# SCH_Flight-Computer-V4_2024-07-19.net
KiCad netlist of a schematic drawn in EasyEDA
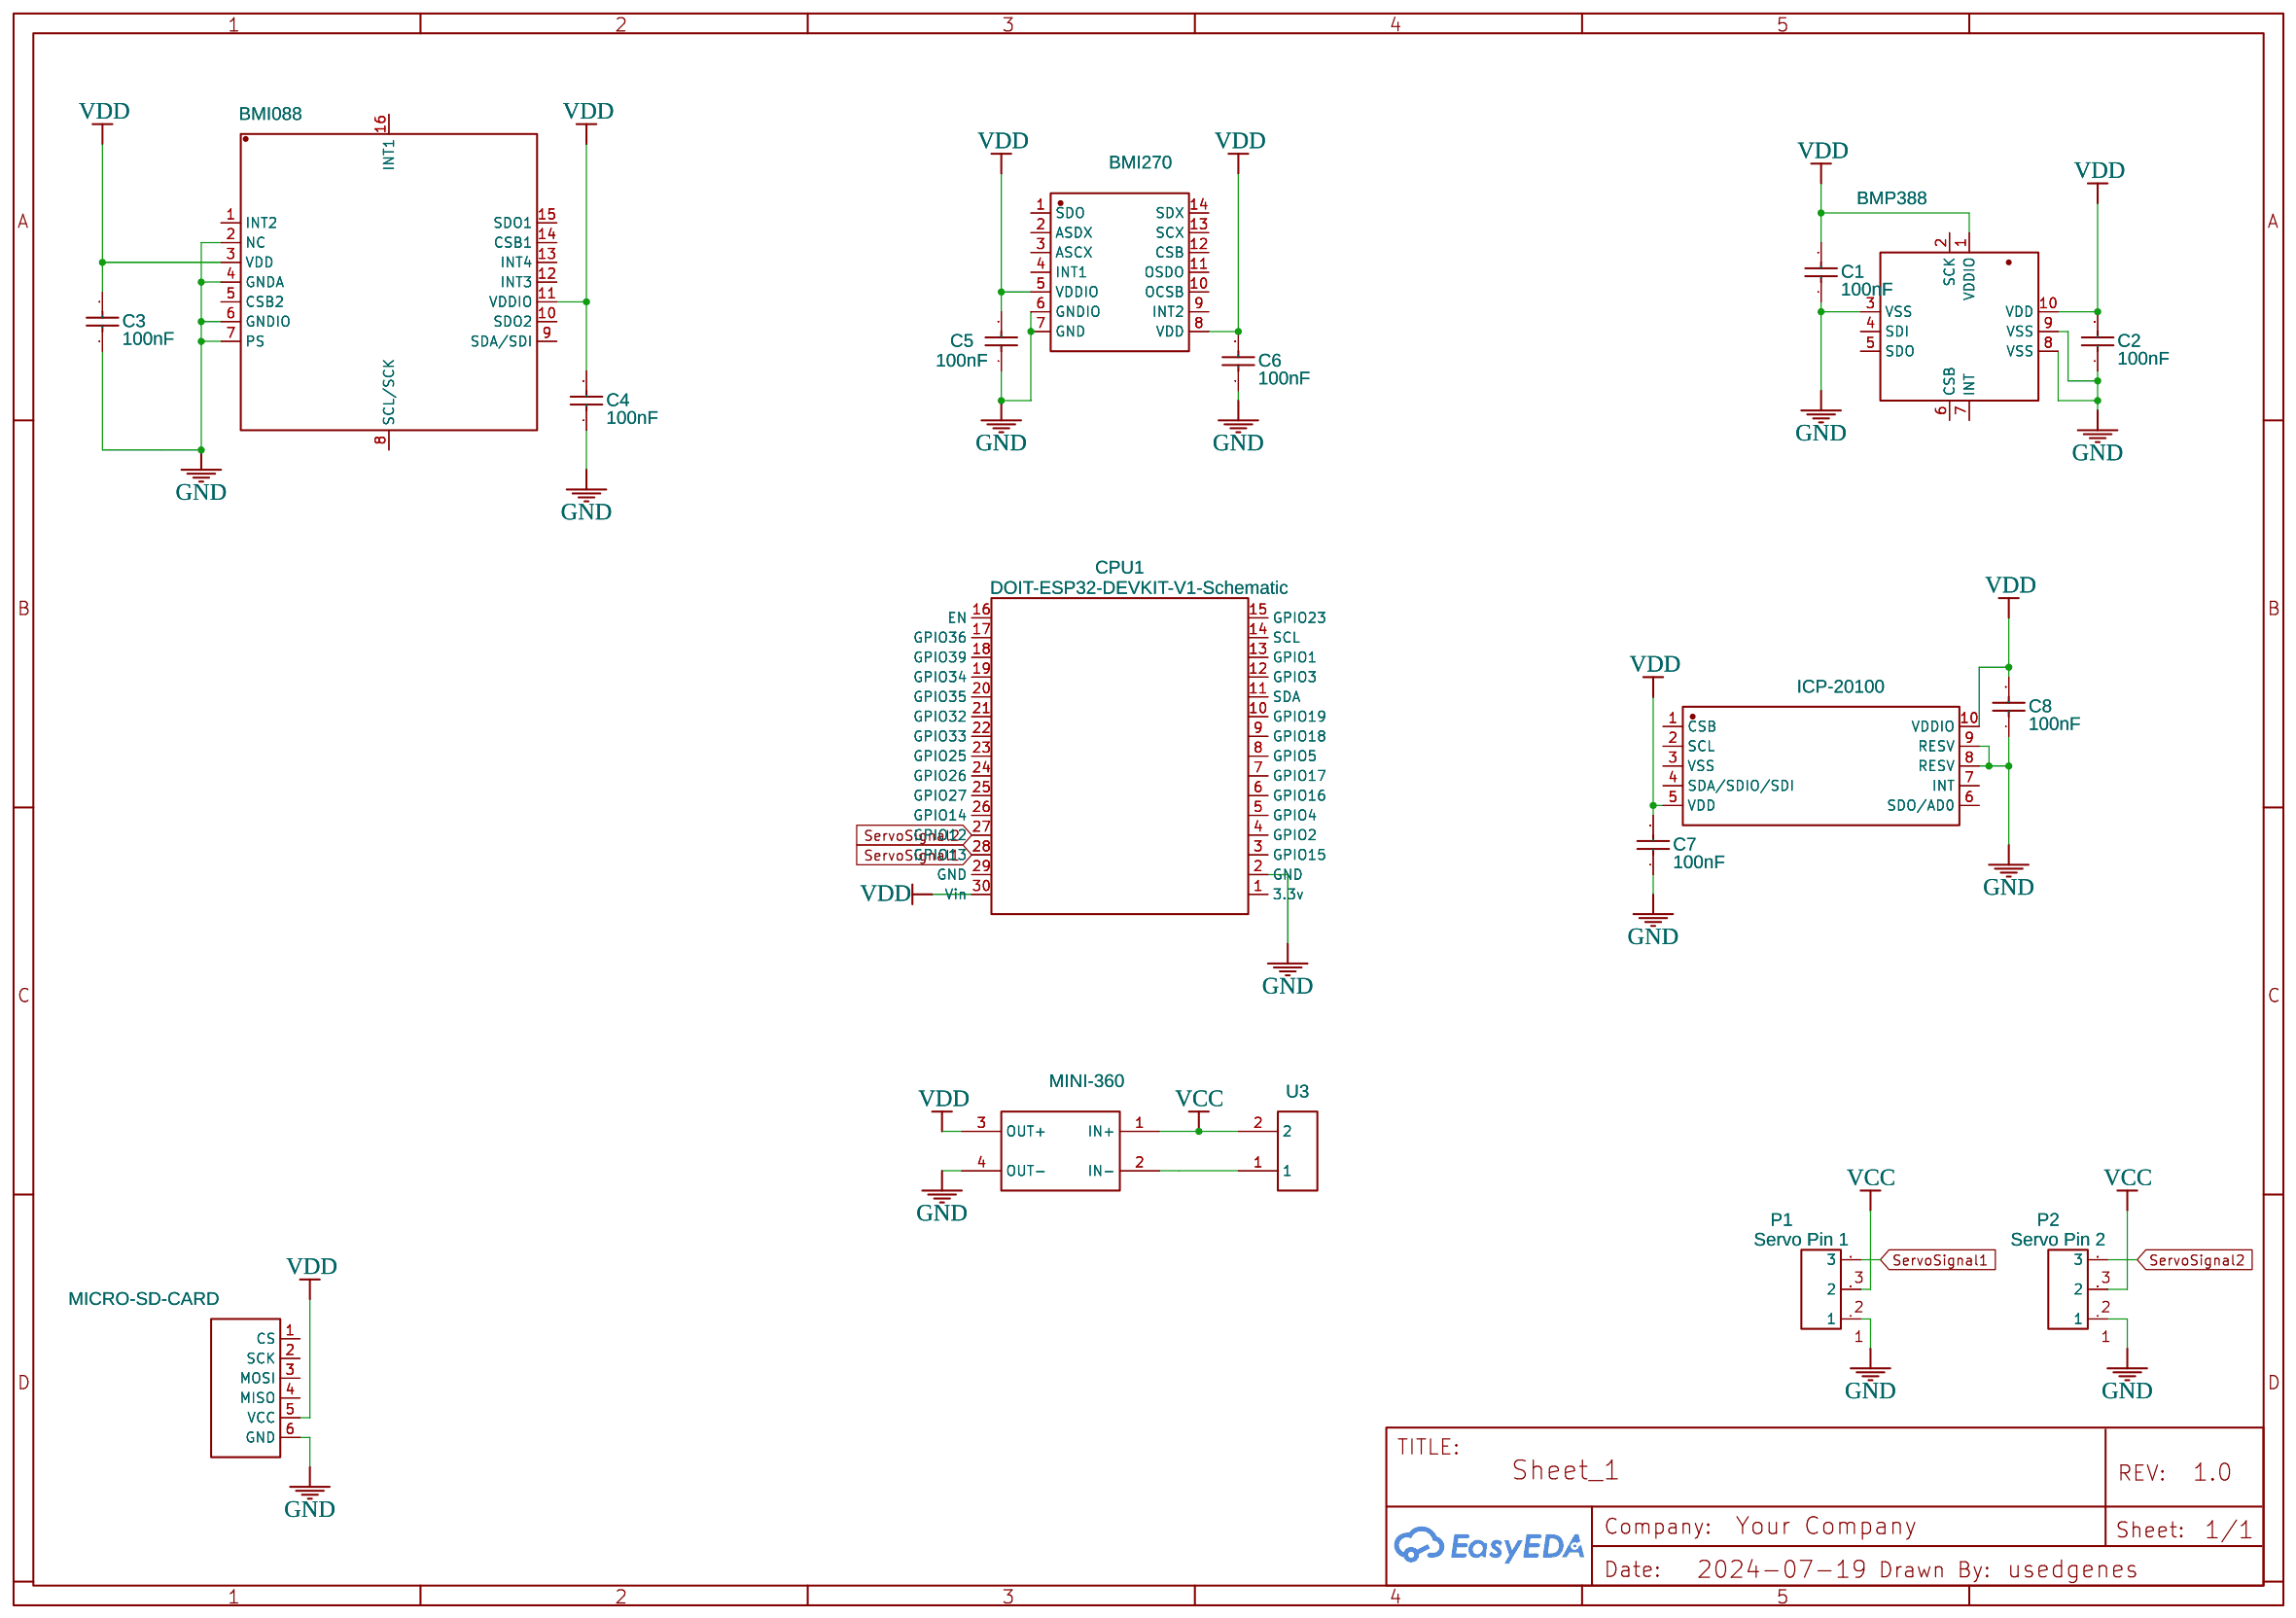
[diagram p0: schematic sheet]

(export (version "E")
  (design (tool "Eeschema 10.0.6"))
  (components
    (comp (ref "BMI088")
      (value "BMI088")
      (fields (field (name "Manufacturer") "Bosch(博世)"))
      (libsource (lib "") (part "BMI088"))
    )
    (comp (ref "BMI270")
      (value "BMI270")
      (fields (field (name "Manufacturer") "Bosch(博世)"))
      (libsource (lib "") (part "BMI270"))
    )
    (comp (ref "BMP388")
      (value "BMP388")
      (fields (field (name "Manufacturer") "Bosch(博世)"))
      (libsource (lib "") (part "BMP388"))
    )
    (comp (ref "C1")
      (value "100nF")
      (fields
        (field (name "Manufacturer Part") "CL05B104KO5NNNC")
        (field (name "Manufacturer") "SAMSUNG(三星)")
      )
      (libsource (lib "") (part "CL05B104KO5NNNC"))
    )
    (comp (ref "C2")
      (value "100nF")
      (fields
        (field (name "Manufacturer Part") "CL05B104KO5NNNC")
        (field (name "Manufacturer") "SAMSUNG(三星)")
      )
      (libsource (lib "") (part "CL05B104KO5NNNC"))
    )
    (comp (ref "C3")
      (value "100nF")
      (fields
        (field (name "Manufacturer Part") "CL05B104KO5NNNC")
        (field (name "Manufacturer") "SAMSUNG(三星)")
      )
      (libsource (lib "") (part "CL05B104KO5NNNC"))
    )
    (comp (ref "C4")
      (value "100nF")
      (fields
        (field (name "Manufacturer Part") "CL05B104KO5NNNC")
        (field (name "Manufacturer") "SAMSUNG(三星)")
      )
      (libsource (lib "") (part "CL05B104KO5NNNC"))
    )
    (comp (ref "C5")
      (value "100nF")
      (fields
        (field (name "Manufacturer Part") "CL05B104KO5NNNC")
        (field (name "Manufacturer") "SAMSUNG(三星)")
      )
      (libsource (lib "") (part "CL05B104KO5NNNC"))
    )
    (comp (ref "C6")
      (value "100nF")
      (fields
        (field (name "Manufacturer Part") "CL05B104KO5NNNC")
        (field (name "Manufacturer") "SAMSUNG(三星)")
      )
      (libsource (lib "") (part "CL05B104KO5NNNC"))
    )
    (comp (ref "C7")
      (value "100nF")
      (fields
        (field (name "Manufacturer Part") "CL05B104KO5NNNC")
        (field (name "Manufacturer") "SAMSUNG(三星)")
      )
      (libsource (lib "") (part "CL05B104KO5NNNC"))
    )
    (comp (ref "C8")
      (value "100nF")
      (fields
        (field (name "Manufacturer Part") "CL05B104KO5NNNC")
        (field (name "Manufacturer") "SAMSUNG(三星)")
      )
      (libsource (lib "") (part "CL05B104KO5NNNC"))
    )
    (comp (ref "CPU1")
      (value "DOIT-ESP32-DEVKIT-V1-Schematic")
      (fields (field (name "Manufacturer Part") "NONE"))
      (libsource (lib "") (part "DOIT-ESP32-DEVKIT-V1-Schematic"))
    )
    (comp (ref "ICP-20100")
      (value "ICP-20100")
      (fields (field (name "Manufacturer") "TDK"))
      (libsource (lib "") (part "ICP-20100"))
    )
    (comp (ref "MICRO-SD-CARD") (value "MicroSDCardAdapter") (libsource (lib "") (part "MicroSDCardAdapter")))
    (comp (ref "MINI-360") (value "MINI-360") (libsource (lib "") (part "MINI-360")))
    (comp (ref "P1")
      (value "Servo Pin 1")
      (fields
        (field (name "Manufacturer Part") "Female headerHDR1X8-2.54")
        (field (name "Manufacturer") "BOOMELE")
      )
      (libsource (lib "") (part "HEADER PAD 3X RMM COPY"))
    )
    (comp (ref "P2")
      (value "Servo Pin 2")
      (fields
        (field (name "Manufacturer Part") "Female headerHDR1X8-2.54")
        (field (name "Manufacturer") "BOOMELE")
      )
      (libsource (lib "") (part "HEADER PAD 3X RMM COPY"))
    )
    (comp (ref "U3") (value "Power Pins") (libsource (lib "") (part "1X2")))
  )
  (nets
    (net (code "1") (name "GND") (class "Default")
      (node (ref "BMI088") (pin "2") (pinfunction "NC_2") (pintype "unspecified"))
      (node (ref "BMI088") (pin "4") (pinfunction "GNDA_4") (pintype "unspecified"))
      (node (ref "BMI088") (pin "6") (pinfunction "GNDIO_6") (pintype "unspecified"))
      (node (ref "BMI088") (pin "7") (pinfunction "PS_7") (pintype "unspecified"))
      (node (ref "BMI270") (pin "6") (pinfunction "GNDIO_6") (pintype "unspecified"))
      (node (ref "BMI270") (pin "7") (pinfunction "GND_7") (pintype "unspecified"))
      (node (ref "BMP388") (pin "3") (pinfunction "VSS_3") (pintype "unspecified"))
      (node (ref "BMP388") (pin "8") (pinfunction "VSS_8") (pintype "unspecified"))
      (node (ref "BMP388") (pin "9") (pinfunction "VSS_9") (pintype "unspecified"))
      (node (ref "C1") (pin "1") (pinfunction "1_1") (pintype "input"))
      (node (ref "C2") (pin "1") (pinfunction "1_1") (pintype "input"))
      (node (ref "C3") (pin "1") (pinfunction "1_1") (pintype "input"))
      (node (ref "C4") (pin "1") (pinfunction "1_1") (pintype "input"))
      (node (ref "C5") (pin "1") (pinfunction "1_1") (pintype "input"))
      (node (ref "C6") (pin "1") (pinfunction "1_1") (pintype "input"))
      (node (ref "C7") (pin "1") (pinfunction "1_1") (pintype "input"))
      (node (ref "C8") (pin "1") (pinfunction "1_1") (pintype "input"))
      (node (ref "CPU1") (pin "2") (pinfunction "GND_2") (pintype "unspecified"))
      (node (ref "ICP-20100") (pin "8") (pinfunction "RESV_8") (pintype "unspecified"))
      (node (ref "ICP-20100") (pin "9") (pinfunction "RESV_9") (pintype "unspecified"))
      (node (ref "MICRO-SD-CARD") (pin "6") (pinfunction "GND_6") (pintype "passive"))
      (node (ref "MINI-360") (pin "4") (pinfunction "OUT-_4") (pintype "unspecified"))
      (node (ref "P1") (pin "1") (pinfunction "1_1") (pintype "unspecified"))
      (node (ref "P2") (pin "1") (pinfunction "1_1") (pintype "unspecified"))
    )
    (net (code "2") (name "Net-(MINI-360-IN-)") (class "Default")
      (node (ref "MINI-360") (pin "2") (pinfunction "IN-_2") (pintype "unspecified"))
      (node (ref "U3") (pin "1") (pinfunction "1_1") (pintype "unspecified"))
    )
    (net (code "3") (name "ServoSignal1") (class "Default")
      (node (ref "CPU1") (pin "28") (pinfunction "GPIO13_28") (pintype "unspecified"))
      (node (ref "P1") (pin "3") (pinfunction "3_3") (pintype "unspecified"))
    )
    (net (code "4") (name "ServoSignal2") (class "Default")
      (node (ref "CPU1") (pin "27") (pinfunction "GPIO12_27") (pintype "unspecified"))
      (node (ref "P2") (pin "3") (pinfunction "3_3") (pintype "unspecified"))
    )
    (net (code "5") (name "VCC") (class "Default")
      (node (ref "MINI-360") (pin "1") (pinfunction "IN+_1") (pintype "unspecified"))
      (node (ref "P1") (pin "2") (pinfunction "2_2") (pintype "unspecified"))
      (node (ref "P2") (pin "2") (pinfunction "2_2") (pintype "unspecified"))
      (node (ref "U3") (pin "2") (pinfunction "2_2") (pintype "unspecified"))
    )
    (net (code "6") (name "VDD") (class "Default")
      (node (ref "BMI088") (pin "11") (pinfunction "VDDIO_11") (pintype "unspecified"))
      (node (ref "BMI088") (pin "3") (pinfunction "VDD_3") (pintype "unspecified"))
      (node (ref "BMI270") (pin "5") (pinfunction "VDDIO_5") (pintype "unspecified"))
      (node (ref "BMI270") (pin "8") (pinfunction "VDD_8") (pintype "unspecified"))
      (node (ref "BMP388") (pin "1") (pinfunction "VDDIO_1") (pintype "unspecified"))
      (node (ref "BMP388") (pin "10") (pinfunction "VDD_10") (pintype "unspecified"))
      (node (ref "C1") (pin "2") (pinfunction "2_2") (pintype "input"))
      (node (ref "C2") (pin "2") (pinfunction "2_2") (pintype "input"))
      (node (ref "C3") (pin "2") (pinfunction "2_2") (pintype "input"))
      (node (ref "C4") (pin "2") (pinfunction "2_2") (pintype "input"))
      (node (ref "C5") (pin "2") (pinfunction "2_2") (pintype "input"))
      (node (ref "C6") (pin "2") (pinfunction "2_2") (pintype "input"))
      (node (ref "C7") (pin "2") (pinfunction "2_2") (pintype "input"))
      (node (ref "C8") (pin "2") (pinfunction "2_2") (pintype "input"))
      (node (ref "CPU1") (pin "30") (pinfunction "Vin_30") (pintype "unspecified"))
      (node (ref "ICP-20100") (pin "10") (pinfunction "VDDIO_10") (pintype "unspecified"))
      (node (ref "ICP-20100") (pin "5") (pinfunction "VDD_5") (pintype "unspecified"))
      (node (ref "MICRO-SD-CARD") (pin "5") (pinfunction "VCC_5") (pintype "passive"))
      (node (ref "MINI-360") (pin "3") (pinfunction "OUT+_3") (pintype "unspecified"))
    )
    (net (code "7") (name "unconnected-(BMI088-CSB1-Pad14)") (class "Default")
      (node (ref "BMI088") (pin "14") (pinfunction "CSB1_14") (pintype "unspecified"))
    )
    (net (code "8") (name "unconnected-(BMI088-CSB2-Pad5)") (class "Default")
      (node (ref "BMI088") (pin "5") (pinfunction "CSB2_5") (pintype "unspecified"))
    )
    (net (code "9") (name "unconnected-(BMI088-INT1-Pad16)") (class "Default")
      (node (ref "BMI088") (pin "16") (pinfunction "INT1_16") (pintype "unspecified"))
    )
    (net (code "10") (name "unconnected-(BMI088-INT2-Pad1)") (class "Default")
      (node (ref "BMI088") (pin "1") (pinfunction "INT2_1") (pintype "unspecified"))
    )
    (net (code "11") (name "unconnected-(BMI088-INT3-Pad12)") (class "Default")
      (node (ref "BMI088") (pin "12") (pinfunction "INT3_12") (pintype "unspecified"))
    )
    (net (code "12") (name "unconnected-(BMI088-INT4-Pad13)") (class "Default")
      (node (ref "BMI088") (pin "13") (pinfunction "INT4_13") (pintype "unspecified"))
    )
    (net (code "13") (name "unconnected-(BMI088-SCL{slash}SCK-Pad8)") (class "Default")
      (node (ref "BMI088") (pin "8") (pinfunction "SCL/SCK_8") (pintype "unspecified"))
    )
    (net (code "14") (name "unconnected-(BMI088-SDA{slash}SDI-Pad9)") (class "Default")
      (node (ref "BMI088") (pin "9") (pinfunction "SDA/SDI_9") (pintype "unspecified"))
    )
    (net (code "15") (name "unconnected-(BMI088-SDO1-Pad15)") (class "Default")
      (node (ref "BMI088") (pin "15") (pinfunction "SDO1_15") (pintype "unspecified"))
    )
    (net (code "16") (name "unconnected-(BMI088-SDO2-Pad10)") (class "Default")
      (node (ref "BMI088") (pin "10") (pinfunction "SDO2_10") (pintype "unspecified"))
    )
    (net (code "17") (name "unconnected-(BMI270-ASCX-Pad3)") (class "Default")
      (node (ref "BMI270") (pin "3") (pinfunction "ASCX_3") (pintype "unspecified"))
    )
    (net (code "18") (name "unconnected-(BMI270-ASDX-Pad2)") (class "Default")
      (node (ref "BMI270") (pin "2") (pinfunction "ASDX_2") (pintype "unspecified"))
    )
    (net (code "19") (name "unconnected-(BMI270-CSB-Pad12)") (class "Default")
      (node (ref "BMI270") (pin "12") (pinfunction "CSB_12") (pintype "unspecified"))
    )
    (net (code "20") (name "unconnected-(BMI270-INT1-Pad4)") (class "Default")
      (node (ref "BMI270") (pin "4") (pinfunction "INT1_4") (pintype "unspecified"))
    )
    (net (code "21") (name "unconnected-(BMI270-INT2-Pad9)") (class "Default")
      (node (ref "BMI270") (pin "9") (pinfunction "INT2_9") (pintype "unspecified"))
    )
    (net (code "22") (name "unconnected-(BMI270-OCSB-Pad10)") (class "Default")
      (node (ref "BMI270") (pin "10") (pinfunction "OCSB_10") (pintype "unspecified"))
    )
    (net (code "23") (name "unconnected-(BMI270-OSDO-Pad11)") (class "Default")
      (node (ref "BMI270") (pin "11") (pinfunction "OSDO_11") (pintype "unspecified"))
    )
    (net (code "24") (name "unconnected-(BMI270-SCX-Pad13)") (class "Default")
      (node (ref "BMI270") (pin "13") (pinfunction "SCX_13") (pintype "unspecified"))
    )
    (net (code "25") (name "unconnected-(BMI270-SDO-Pad1)") (class "Default")
      (node (ref "BMI270") (pin "1") (pinfunction "SDO_1") (pintype "unspecified"))
    )
    (net (code "26") (name "unconnected-(BMI270-SDX-Pad14)") (class "Default")
      (node (ref "BMI270") (pin "14") (pinfunction "SDX_14") (pintype "unspecified"))
    )
    (net (code "27") (name "unconnected-(BMP388-CSB-Pad6)") (class "Default")
      (node (ref "BMP388") (pin "6") (pinfunction "CSB_6") (pintype "unspecified"))
    )
    (net (code "28") (name "unconnected-(BMP388-INT-Pad7)") (class "Default")
      (node (ref "BMP388") (pin "7") (pinfunction "INT_7") (pintype "unspecified"))
    )
    (net (code "29") (name "unconnected-(BMP388-SCK-Pad2)") (class "Default")
      (node (ref "BMP388") (pin "2") (pinfunction "SCK_2") (pintype "unspecified"))
    )
    (net (code "30") (name "unconnected-(BMP388-SDI-Pad4)") (class "Default")
      (node (ref "BMP388") (pin "4") (pinfunction "SDI_4") (pintype "unspecified"))
    )
    (net (code "31") (name "unconnected-(BMP388-SDO-Pad5)") (class "Default")
      (node (ref "BMP388") (pin "5") (pinfunction "SDO_5") (pintype "unspecified"))
    )
    (net (code "32") (name "unconnected-(CPU1-3.3v-Pad1)") (class "Default")
      (node (ref "CPU1") (pin "1") (pinfunction "3.3v_1") (pintype "unspecified"))
    )
    (net (code "33") (name "unconnected-(CPU1-EN-Pad16)") (class "Default")
      (node (ref "CPU1") (pin "16") (pinfunction "EN_16") (pintype "unspecified"))
    )
    (net (code "34") (name "unconnected-(CPU1-GND-Pad29)") (class "Default")
      (node (ref "CPU1") (pin "29") (pinfunction "GND_29") (pintype "unspecified"))
    )
    (net (code "35") (name "unconnected-(CPU1-GPIO1-Pad13)") (class "Default")
      (node (ref "CPU1") (pin "13") (pinfunction "GPIO1_13") (pintype "unspecified"))
    )
    (net (code "36") (name "unconnected-(CPU1-GPIO2-Pad4)") (class "Default")
      (node (ref "CPU1") (pin "4") (pinfunction "GPIO2_4") (pintype "unspecified"))
    )
    (net (code "37") (name "unconnected-(CPU1-GPIO3-Pad12)") (class "Default")
      (node (ref "CPU1") (pin "12") (pinfunction "GPIO3_12") (pintype "unspecified"))
    )
    (net (code "38") (name "unconnected-(CPU1-GPIO4-Pad5)") (class "Default")
      (node (ref "CPU1") (pin "5") (pinfunction "GPIO4_5") (pintype "unspecified"))
    )
    (net (code "39") (name "unconnected-(CPU1-GPIO5-Pad8)") (class "Default")
      (node (ref "CPU1") (pin "8") (pinfunction "GPIO5_8") (pintype "unspecified"))
    )
    (net (code "40") (name "unconnected-(CPU1-GPIO14-Pad26)") (class "Default")
      (node (ref "CPU1") (pin "26") (pinfunction "GPIO14_26") (pintype "unspecified"))
    )
    (net (code "41") (name "unconnected-(CPU1-GPIO15-Pad3)") (class "Default")
      (node (ref "CPU1") (pin "3") (pinfunction "GPIO15_3") (pintype "unspecified"))
    )
    (net (code "42") (name "unconnected-(CPU1-GPIO16-Pad6)") (class "Default")
      (node (ref "CPU1") (pin "6") (pinfunction "GPIO16_6") (pintype "unspecified"))
    )
    (net (code "43") (name "unconnected-(CPU1-GPIO17-Pad7)") (class "Default")
      (node (ref "CPU1") (pin "7") (pinfunction "GPIO17_7") (pintype "unspecified"))
    )
    (net (code "44") (name "unconnected-(CPU1-GPIO18-Pad9)") (class "Default")
      (node (ref "CPU1") (pin "9") (pinfunction "GPIO18_9") (pintype "unspecified"))
    )
    (net (code "45") (name "unconnected-(CPU1-GPIO19-Pad10)") (class "Default")
      (node (ref "CPU1") (pin "10") (pinfunction "GPIO19_10") (pintype "unspecified"))
    )
    (net (code "46") (name "unconnected-(CPU1-GPIO23-Pad15)") (class "Default")
      (node (ref "CPU1") (pin "15") (pinfunction "GPIO23_15") (pintype "unspecified"))
    )
    (net (code "47") (name "unconnected-(CPU1-GPIO25-Pad23)") (class "Default")
      (node (ref "CPU1") (pin "23") (pinfunction "GPIO25_23") (pintype "unspecified"))
    )
    (net (code "48") (name "unconnected-(CPU1-GPIO26-Pad24)") (class "Default")
      (node (ref "CPU1") (pin "24") (pinfunction "GPIO26_24") (pintype "unspecified"))
    )
    (net (code "49") (name "unconnected-(CPU1-GPIO27-Pad25)") (class "Default")
      (node (ref "CPU1") (pin "25") (pinfunction "GPIO27_25") (pintype "unspecified"))
    )
    (net (code "50") (name "unconnected-(CPU1-GPIO32-Pad21)") (class "Default")
      (node (ref "CPU1") (pin "21") (pinfunction "GPIO32_21") (pintype "unspecified"))
    )
    (net (code "51") (name "unconnected-(CPU1-GPIO33-Pad22)") (class "Default")
      (node (ref "CPU1") (pin "22") (pinfunction "GPIO33_22") (pintype "unspecified"))
    )
    (net (code "52") (name "unconnected-(CPU1-GPIO34-Pad19)") (class "Default")
      (node (ref "CPU1") (pin "19") (pinfunction "GPIO34_19") (pintype "unspecified"))
    )
    (net (code "53") (name "unconnected-(CPU1-GPIO35-Pad20)") (class "Default")
      (node (ref "CPU1") (pin "20") (pinfunction "GPIO35_20") (pintype "unspecified"))
    )
    (net (code "54") (name "unconnected-(CPU1-GPIO36-Pad17)") (class "Default")
      (node (ref "CPU1") (pin "17") (pinfunction "GPIO36_17") (pintype "unspecified"))
    )
    (net (code "55") (name "unconnected-(CPU1-GPIO39-Pad18)") (class "Default")
      (node (ref "CPU1") (pin "18") (pinfunction "GPIO39_18") (pintype "unspecified"))
    )
    (net (code "56") (name "unconnected-(CPU1-SCL-Pad14)") (class "Default")
      (node (ref "CPU1") (pin "14") (pinfunction "SCL_14") (pintype "unspecified"))
    )
    (net (code "57") (name "unconnected-(CPU1-SDA-Pad11)") (class "Default")
      (node (ref "CPU1") (pin "11") (pinfunction "SDA_11") (pintype "unspecified"))
    )
    (net (code "58") (name "unconnected-(ICP-20100-CSB-Pad1)") (class "Default")
      (node (ref "ICP-20100") (pin "1") (pinfunction "CSB_1") (pintype "unspecified"))
    )
    (net (code "59") (name "unconnected-(ICP-20100-INT-Pad7)") (class "Default")
      (node (ref "ICP-20100") (pin "7") (pinfunction "INT_7") (pintype "unspecified"))
    )
    (net (code "60") (name "unconnected-(ICP-20100-SCL-Pad2)") (class "Default")
      (node (ref "ICP-20100") (pin "2") (pinfunction "SCL_2") (pintype "unspecified"))
    )
    (net (code "61") (name "unconnected-(ICP-20100-SDA{slash}SDIO{slash}SDI-Pad4)") (class "Default")
      (node (ref "ICP-20100") (pin "4") (pinfunction "SDA/SDIO/SDI_4") (pintype "unspecified"))
    )
    (net (code "62") (name "unconnected-(ICP-20100-SDO{slash}AD0-Pad6)") (class "Default")
      (node (ref "ICP-20100") (pin "6") (pinfunction "SDO/AD0_6") (pintype "unspecified"))
    )
    (net (code "63") (name "unconnected-(ICP-20100-VSS-Pad3)") (class "Default")
      (node (ref "ICP-20100") (pin "3") (pinfunction "VSS_3") (pintype "unspecified"))
    )
    (net (code "64") (name "unconnected-(MICRO-SD-CARD-CS-Pad1)") (class "Default")
      (node (ref "MICRO-SD-CARD") (pin "1") (pinfunction "CS_1") (pintype "bidirectional"))
    )
    (net (code "65") (name "unconnected-(MICRO-SD-CARD-MISO-Pad4)") (class "Default")
      (node (ref "MICRO-SD-CARD") (pin "4") (pinfunction "MISO_4") (pintype "bidirectional"))
    )
    (net (code "66") (name "unconnected-(MICRO-SD-CARD-MOSI-Pad3)") (class "Default")
      (node (ref "MICRO-SD-CARD") (pin "3") (pinfunction "MOSI_3") (pintype "passive"))
    )
    (net (code "67") (name "unconnected-(MICRO-SD-CARD-SCK-Pad2)") (class "Default")
      (node (ref "MICRO-SD-CARD") (pin "2") (pinfunction "SCK_2") (pintype "bidirectional"))
    )
  )
)
